# EU_Power_Management.net
KiCad netlist of a schematic drawn in Altium Designer
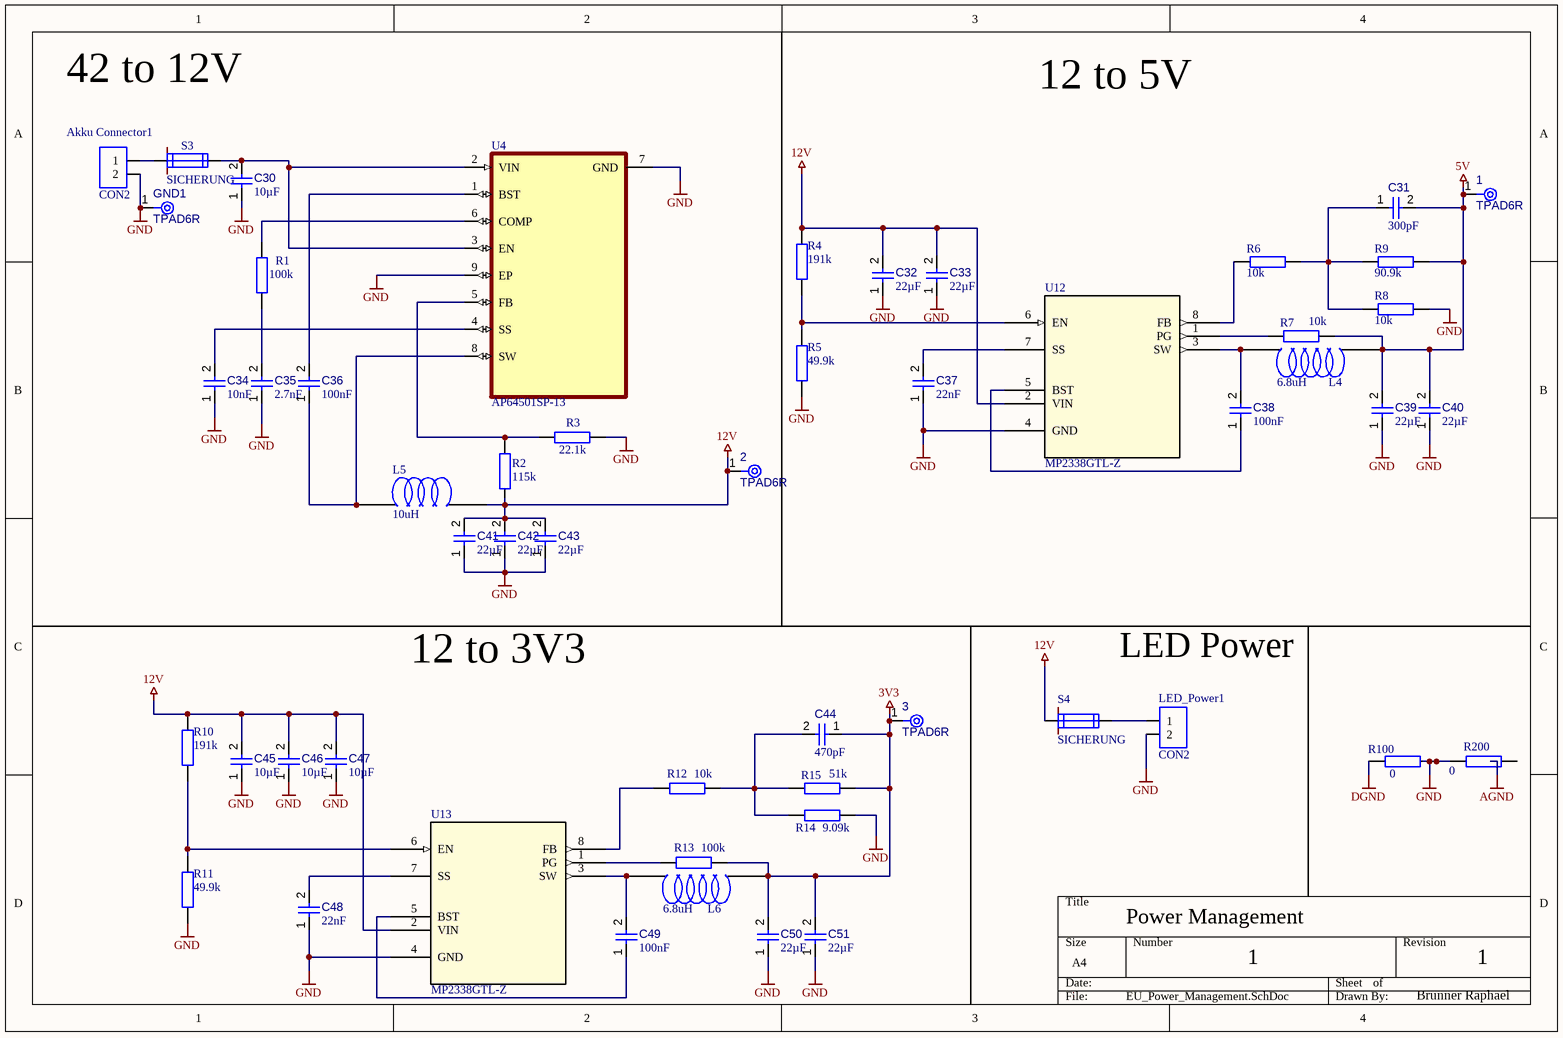
[diagram p0: EU_Power_Management.SchDoc]

(export (version "E")
  (design (tool "Eeschema 10.0.6"))
  (components
    (comp (ref "1")
      (value "TPAD6R")
      (footprint "TP06R")
      (description "0.6mm round")
      (libsource (lib " L-PRAN") (part "CMP-001-0001-4"))
    )
    (comp (ref "2")
      (value "TPAD6R")
      (footprint "TP06R")
      (description "0.6mm round")
      (libsource (lib " L-PRAN") (part "CMP-001-0001-4"))
    )
    (comp (ref "3")
      (value "TPAD6R")
      (footprint "TP06R")
      (description "0.6mm round")
      (libsource (lib " L-PRAN") (part "CMP-001-0001-4"))
    )
    (comp (ref "Akku Connector1")
      (value "CON2")
      (footprint "SIP-2")
      (description "Stecker")
      (libsource (lib "HTL-sym-2021_04") (part "CON2"))
    )
    (comp (ref "C30")
      (value "10µF")
      (footprint "CAPC0603(1608)100_L")
      (description "Chip Capacitor, 10µF +/-20%, 10V, 0603, Thickness 1 mm")
      (fields (field (name "TOLERANCE") "10%") (field (name "Comment") "Capacitor 10µF +/-20% 10V 0603"))
      (libsource (lib " L-PRAN") (part "CAP-NP-2"))
    )
    (comp (ref "C31")
      (value "300pF")
      (footprint "CAPC1608X90X40NL10T20")
      (description "Chip Capacitor, 100 nF, +/- 10%, 50 V, 0603 (1608 Metric)")
      (fields (field (name "TOLERANCE") "10%") (field (name "Comment") "Capacitor 100 nF +/-10% 50 V 0603"))
      (libsource (lib " L-PRAN") (part "CAP-NP-2"))
    )
    (comp (ref "C32")
      (value "22µF")
      (footprint "CAPC0805(2012)145_L")
      (description "Chip Capacitor, 22µF +/-40%, 16V, 0805, Thickness 1.45 mm")
      (fields (field (name "TOLERANCE") "5%") (field (name "Comment") "Capacitor 22µF +/-40% 16V 0805"))
      (libsource (lib " L-PRAN") (part "CAP-NP-2"))
    )
    (comp (ref "C33")
      (value "22µF")
      (footprint "CAPC0805(2012)145_L")
      (description "Chip Capacitor, 22µF +/-40%, 16V, 0805, Thickness 1.45 mm")
      (fields (field (name "TOLERANCE") "5%") (field (name "Comment") "Capacitor 22µF +/-40% 16V 0805"))
      (libsource (lib " L-PRAN") (part "CAP-NP-2"))
    )
    (comp (ref "C34")
      (value "10nF")
      (footprint "CAPC1608X94X35NL15T15")
      (description "Chip Capacitor, 1 uF, +/- 10%, 16 V, 0603 (1608 Metric)")
      (fields (field (name "TOLERANCE") "10%"))
      (libsource (lib " L-PRAN") (part "CAP-NP-2"))
    )
    (comp (ref "C35")
      (value "2.7nF")
      (footprint "CAPC1608X94X35NL15T15")
      (description "Chip Capacitor, 1 uF, +/- 10%, 16 V, 0603 (1608 Metric)")
      (fields (field (name "TOLERANCE") "10%"))
      (libsource (lib " L-PRAN") (part "CAP-NP-2"))
    )
    (comp (ref "C36")
      (value "100nF")
      (footprint "CAPC1608X94X35NL15T15")
      (description "Chip Capacitor, 1 uF, +/- 10%, 16 V, 0603 (1608 Metric)")
      (fields (field (name "TOLERANCE") "10%") (field (name "Comment") "0.1uF"))
      (libsource (lib " L-PRAN") (part "CAP-NP-2"))
    )
    (comp (ref "C37")
      (value "22nF")
      (footprint "CAPC0402(1005)60_L")
      (description "Chip Capacitor, 22nF +/-20%, 10V, 0402, Thickness 0.6 mm")
      (fields (field (name "TOLERANCE") "10%") (field (name "Comment") "Capacitor 22nF +/-20% 10V 0402"))
      (libsource (lib " L-PRAN") (part "CAP-NP-2"))
    )
    (comp (ref "C38")
      (value "100nF")
      (footprint "CAPC1608X90X40NL10T20")
      (description "Chip Capacitor, 100 nF, +/- 10%, 50 V, 0603 (1608 Metric)")
      (fields (field (name "TOLERANCE") "10%") (field (name "Comment") "Capacitor 100 nF +/-10% 50 V 0603"))
      (libsource (lib " L-PRAN") (part "CAP-NP-2"))
    )
    (comp (ref "C39")
      (value "22µF")
      (footprint "CAPC0805(2012)145_L")
      (description "Chip Capacitor, 22µF +/-40%, 16V, 0805, Thickness 1.45 mm")
      (fields (field (name "TOLERANCE") "5%") (field (name "Comment") "Capacitor 22µF +/-40% 16V 0805"))
      (libsource (lib " L-PRAN") (part "CAP-NP-2"))
    )
    (comp (ref "C40")
      (value "22µF")
      (footprint "CAPC0805(2012)145_L")
      (description "Chip Capacitor, 22µF +/-40%, 16V, 0805, Thickness 1.45 mm")
      (fields (field (name "TOLERANCE") "5%") (field (name "Comment") "Capacitor 22µF +/-40% 16V 0805"))
      (libsource (lib " L-PRAN") (part "CAP-NP-2"))
    )
    (comp (ref "C41")
      (value "22µF")
      (footprint "CAPC0805(2012)145_L")
      (description "Chip Capacitor, 22µF +/-40%, 16V, 0805, Thickness 1.45 mm")
      (fields (field (name "TOLERANCE") "5%") (field (name "Comment") "Capacitor 22µF +/-40% 16V 0805"))
      (libsource (lib " L-PRAN") (part "CAP-NP-2"))
    )
    (comp (ref "C42")
      (value "22µF")
      (footprint "CAPC0805(2012)145_L")
      (description "Chip Capacitor, 22µF +/-40%, 16V, 0805, Thickness 1.45 mm")
      (fields (field (name "TOLERANCE") "5%") (field (name "Comment") "Capacitor 22µF +/-40% 16V 0805"))
      (libsource (lib " L-PRAN") (part "CAP-NP-2"))
    )
    (comp (ref "C43")
      (value "22µF")
      (footprint "CAPC0805(2012)145_L")
      (description "Chip Capacitor, 22µF +/-40%, 16V, 0805, Thickness 1.45 mm")
      (fields (field (name "TOLERANCE") "5%") (field (name "Comment") "Capacitor 22µF +/-40% 16V 0805"))
      (libsource (lib " L-PRAN") (part "CAP-NP-2"))
    )
    (comp (ref "C44")
      (value "470pF")
      (footprint "CAPC1608X90X40NL10T20")
      (description "Chip Capacitor, 100 nF, +/- 10%, 50 V, 0603 (1608 Metric)")
      (fields (field (name "TOLERANCE") "10%") (field (name "Comment") "Capacitor 100 nF +/-10% 50 V 0603"))
      (libsource (lib " L-PRAN") (part "CAP-NP-2"))
    )
    (comp (ref "C45")
      (value "10µF")
      (footprint "CAPC0603(1608)100_L")
      (description "Chip Capacitor, 10µF +/-20%, 10V, 0603, Thickness 1 mm")
      (fields (field (name "TOLERANCE") "10%") (field (name "Comment") "Capacitor 10µF +/-20% 10V 0603"))
      (libsource (lib " L-PRAN") (part "CAP-NP-2"))
    )
    (comp (ref "C46")
      (value "10µF")
      (footprint "CAPC0603(1608)100_L")
      (description "Chip Capacitor, 10µF +/-20%, 10V, 0603, Thickness 1 mm")
      (fields (field (name "TOLERANCE") "10%") (field (name "Comment") "Capacitor 10µF +/-20% 10V 0603"))
      (libsource (lib " L-PRAN") (part "CAP-NP-2"))
    )
    (comp (ref "C47")
      (value "10µF")
      (footprint "CAPC0603(1608)100_L")
      (description "Chip Capacitor, 10µF +/-20%, 10V, 0603, Thickness 1 mm")
      (fields (field (name "TOLERANCE") "10%") (field (name "Comment") "Capacitor 10µF +/-20% 10V 0603"))
      (libsource (lib " L-PRAN") (part "CAP-NP-2"))
    )
    (comp (ref "C48")
      (value "22nF")
      (footprint "CAPC1608X90X40NL10T20")
      (description "Chip Capacitor, 100 nF, +/- 10%, 50 V, 0603 (1608 Metric)")
      (fields (field (name "TOLERANCE") "10%") (field (name "Comment") "Capacitor 100 nF +/-10% 50 V 0603"))
      (libsource (lib " L-PRAN") (part "CAP-NP-2"))
    )
    (comp (ref "C49")
      (value "100nF")
      (footprint "CAPC1608X90X40NL10T20")
      (description "Chip Capacitor, 100 nF, +/- 10%, 50 V, 0603 (1608 Metric)")
      (fields (field (name "TOLERANCE") "10%") (field (name "Comment") "Capacitor 100 nF +/-10% 50 V 0603"))
      (libsource (lib " L-PRAN") (part "CAP-NP-2"))
    )
    (comp (ref "C50")
      (value "22µF")
      (footprint "CAPC0805(2012)145_L")
      (description "Chip Capacitor, 22µF +/-40%, 16V, 0805, Thickness 1.45 mm")
      (fields (field (name "TOLERANCE") "5%") (field (name "Comment") "Capacitor 22µF +/-40% 16V 0805"))
      (libsource (lib " L-PRAN") (part "CAP-NP-2"))
    )
    (comp (ref "C51")
      (value "22µF")
      (footprint "CAPC0805(2012)145_L")
      (description "Chip Capacitor, 22µF +/-40%, 16V, 0805, Thickness 1.45 mm")
      (fields (field (name "TOLERANCE") "5%") (field (name "Comment") "Capacitor 22µF +/-40% 16V 0805"))
      (libsource (lib " L-PRAN") (part "CAP-NP-2"))
    )
    (comp (ref "GND1")
      (value "TPAD6R")
      (footprint "TP06R")
      (description "0.6mm round")
      (libsource (lib " L-PRAN") (part "CMP-001-0001-4"))
    )
    (comp (ref "L4")
      (value "6.8uH")
      (footprint "MPL-AL6060")
      (libsource (lib "Coil 6.8uH") (part "Component_1"))
    )
    (comp (ref "L5")
      (value "10uH")
      (footprint "MPL-AY1050")
      (libsource (lib "Coil 10uH") (part "Component_1"))
    )
    (comp (ref "L6")
      (value "6.8uH")
      (footprint "MPL-AL6060")
      (libsource (lib "Coil 6.8uH") (part "Component_1"))
    )
    (comp (ref "LED_Power1")
      (value "CON2")
      (footprint "SIP-2")
      (description "Stecker")
      (libsource (lib "HTL-sym-2021_04") (part "CON2"))
    )
    (comp (ref "R1")
      (value "100k")
      (footprint "Axial-0.4")
      (description "Widerstand")
      (fields (field (name "Comment") "RES"))
      (libsource (lib "HTL-sym-2021_04") (part "RES"))
    )
    (comp (ref "R2")
      (value "115k")
      (footprint "Axial-0.4")
      (description "Widerstand")
      (fields (field (name "Comment") "RES"))
      (libsource (lib "HTL-sym-2021_04") (part "RES"))
    )
    (comp (ref "R3")
      (value "22.1k")
      (footprint "Axial-0.4")
      (description "Widerstand")
      (fields (field (name "Comment") "RES"))
      (libsource (lib "HTL-sym-2021_04") (part "RES"))
    )
    (comp (ref "R4")
      (value "191k")
      (footprint "Axial-0.4")
      (description "Widerstand")
      (fields (field (name "Comment") "RES"))
      (libsource (lib "HTL-sym-2021_04") (part "RES"))
    )
    (comp (ref "R5")
      (value "49.9k")
      (footprint "Axial-0.4")
      (description "Widerstand")
      (fields (field (name "Comment") "RES"))
      (libsource (lib "HTL-sym-2021_04") (part "RES"))
    )
    (comp (ref "R6")
      (value "10k")
      (footprint "Axial-0.4")
      (description "Widerstand")
      (fields (field (name "Comment") "RES"))
      (libsource (lib "HTL-sym-2021_04") (part "RES"))
    )
    (comp (ref "R7")
      (value "10k")
      (footprint "Axial-0.4")
      (description "Widerstand")
      (fields (field (name "Comment") "RES"))
      (libsource (lib "HTL-sym-2021_04") (part "RES"))
    )
    (comp (ref "R8")
      (value "10k")
      (footprint "Axial-0.4")
      (description "Widerstand")
      (fields (field (name "Comment") "RES"))
      (libsource (lib "HTL-sym-2021_04") (part "RES"))
    )
    (comp (ref "R9")
      (value "90.9k")
      (footprint "Axial-0.4")
      (description "Widerstand")
      (fields (field (name "Comment") "RES"))
      (libsource (lib "HTL-sym-2021_04") (part "RES"))
    )
    (comp (ref "R10")
      (value "191k")
      (footprint "Axial-0.4")
      (description "Widerstand")
      (fields (field (name "Comment") "RES"))
      (libsource (lib "HTL-sym-2021_04") (part "RES"))
    )
    (comp (ref "R11")
      (value "49.9k")
      (footprint "Axial-0.4")
      (description "Widerstand")
      (fields (field (name "Comment") "RES"))
      (libsource (lib "HTL-sym-2021_04") (part "RES"))
    )
    (comp (ref "R12")
      (value "10k")
      (footprint "Axial-0.4")
      (description "Widerstand")
      (fields (field (name "Comment") "RES"))
      (libsource (lib "HTL-sym-2021_04") (part "RES"))
    )
    (comp (ref "R13")
      (value "100k")
      (footprint "Axial-0.4")
      (description "Widerstand")
      (fields (field (name "Comment") "RES"))
      (libsource (lib "HTL-sym-2021_04") (part "RES"))
    )
    (comp (ref "R14")
      (value "9.09k")
      (footprint "Axial-0.4")
      (description "Widerstand")
      (fields (field (name "Comment") "RES"))
      (libsource (lib "HTL-sym-2021_04") (part "RES"))
    )
    (comp (ref "R15")
      (value "51k")
      (footprint "Axial-0.4")
      (description "Widerstand")
      (fields (field (name "Comment") "RES"))
      (libsource (lib "HTL-sym-2021_04") (part "RES"))
    )
    (comp (ref "R100")
      (value "0")
      (footprint "Axial-0.4")
      (description "Widerstand")
      (fields (field (name "Comment") "RES"))
      (libsource (lib "HTL-sym-2021_04") (part "RES"))
    )
    (comp (ref "R200")
      (value "0")
      (footprint "Axial-0.4")
      (description "Widerstand")
      (fields (field (name "Comment") "RES"))
      (libsource (lib "HTL-sym-2021_04") (part "RES"))
    )
    (comp (ref "S3")
      (value "SICHERUNG")
      (footprint "SICHERUNG")
      (description "Sicherung")
      (libsource (lib "HTL-sym-2021_04") (part "SICHERUNG"))
    )
    (comp (ref "S4")
      (value "SICHERUNG")
      (footprint "SICHERUNG")
      (description "Sicherung")
      (libsource (lib "HTL-sym-2021_04") (part "SICHERUNG"))
    )
    (comp (ref "U4")
      (value "AP64501SP-13")
      (footprint "AP64501SP-13:SOIC127P600X170-9N")
      (fields (field (name "MF") "{'manufacturer': u'Diodes Incorporated'}"))
      (libsource (lib "*") (part "AP64501SP-13"))
    )
    (comp (ref "U12")
      (value "MP2338GTL-Z")
      (footprint "SOT583_MP2338_MNP")
      (description "High-Efficiency 28V 3A 450kHz Synchronous Step-Down Converter In SOT583 Package")
      (fields (field (name "COPYRIGHT") "Copyright (C) 2025 Ultra Librarian. All rights reserved."))
      (libsource (lib "MP2338GTL-Z") (part "MP2338GTL-Z"))
    )
    (comp (ref "U13")
      (value "MP2338GTL-Z")
      (footprint "SOT583_MP2338_MNP")
      (description "High-Efficiency 28V 3A 450kHz Synchronous Step-Down Converter In SOT583 Package")
      (fields (field (name "COPYRIGHT") "Copyright (C) 2025 Ultra Librarian. All rights reserved."))
      (libsource (lib "MP2338GTL-Z") (part "MP2338GTL-Z"))
    )
  )
  (nets
    (net (code "1") (name "3V3") (class "Default")
      (node (ref "3") (pin "1") (pinfunction "TP_1") (pintype "passive"))
      (node (ref "C44") (pin "1") (pinfunction "1_1") (pintype "passive"))
      (node (ref "C50") (pin "2") (pinfunction "2_2") (pintype "passive"))
      (node (ref "C51") (pin "2") (pinfunction "2_2") (pintype "passive"))
      (node (ref "L6") (pin "2") (pinfunction "2_2") (pintype "passive"))
      (node (ref "R13") (pin "2") (pintype "passive"))
      (node (ref "R15") (pin "2") (pintype "passive"))
    )
    (net (code "2") (name "5V") (class "Default")
      (node (ref "1") (pin "1") (pinfunction "TP_1") (pintype "passive"))
      (node (ref "C31") (pin "2") (pinfunction "2_2") (pintype "passive"))
      (node (ref "C39") (pin "2") (pinfunction "2_2") (pintype "passive"))
      (node (ref "C40") (pin "2") (pinfunction "2_2") (pintype "passive"))
      (node (ref "L4") (pin "2") (pinfunction "2_2") (pintype "passive"))
      (node (ref "R7") (pin "1") (pintype "passive"))
      (node (ref "R9") (pin "1") (pintype "passive"))
    )
    (net (code "3") (name "12V") (class "Default")
      (node (ref "2") (pin "1") (pinfunction "TP_1") (pintype "passive"))
      (node (ref "C32") (pin "2") (pinfunction "2_2") (pintype "passive"))
      (node (ref "C33") (pin "2") (pinfunction "2_2") (pintype "passive"))
      (node (ref "C41") (pin "2") (pinfunction "2_2") (pintype "passive"))
      (node (ref "C42") (pin "2") (pinfunction "2_2") (pintype "passive"))
      (node (ref "C43") (pin "2") (pinfunction "2_2") (pintype "passive"))
      (node (ref "C45") (pin "2") (pinfunction "2_2") (pintype "passive"))
      (node (ref "C46") (pin "2") (pinfunction "2_2") (pintype "passive"))
      (node (ref "C47") (pin "2") (pinfunction "2_2") (pintype "passive"))
      (node (ref "L5") (pin "2") (pinfunction "2_2") (pintype "passive"))
      (node (ref "R10") (pin "1") (pintype "passive"))
      (node (ref "R2") (pin "2") (pintype "passive"))
      (node (ref "R4") (pin "2") (pintype "passive"))
      (node (ref "S4") (pin "1") (pintype "passive"))
      (node (ref "U12") (pin "2") (pinfunction "VIN_2") (pintype "power_in"))
      (node (ref "U13") (pin "2") (pinfunction "VIN_2") (pintype "power_in"))
    )
    (net (code "5") (name "DGND") (class "Default") (node (ref "R100") (pin "1") (pintype "passive")))
    (net (code "6") (name "GND") (class "Default")
      (node (ref "Akku Connector1") (pin "2") (pinfunction "2_2") (pintype "passive"))
      (node (ref "C30") (pin "1") (pinfunction "1_1") (pintype "passive"))
      (node (ref "C32") (pin "1") (pinfunction "1_1") (pintype "passive"))
      (node (ref "C33") (pin "1") (pinfunction "1_1") (pintype "passive"))
      (node (ref "C34") (pin "1") (pinfunction "1_1") (pintype "passive"))
      (node (ref "C35") (pin "1") (pinfunction "1_1") (pintype "passive"))
      (node (ref "C37") (pin "1") (pinfunction "1_1") (pintype "passive"))
      (node (ref "C39") (pin "1") (pinfunction "1_1") (pintype "passive"))
      (node (ref "C40") (pin "1") (pinfunction "1_1") (pintype "passive"))
      (node (ref "C41") (pin "1") (pinfunction "1_1") (pintype "passive"))
      (node (ref "C42") (pin "1") (pinfunction "1_1") (pintype "passive"))
      (node (ref "C43") (pin "1") (pinfunction "1_1") (pintype "passive"))
      (node (ref "C45") (pin "1") (pinfunction "1_1") (pintype "passive"))
      (node (ref "C46") (pin "1") (pinfunction "1_1") (pintype "passive"))
      (node (ref "C47") (pin "1") (pinfunction "1_1") (pintype "passive"))
      (node (ref "C48") (pin "1") (pinfunction "1_1") (pintype "passive"))
      (node (ref "C50") (pin "1") (pinfunction "1_1") (pintype "passive"))
      (node (ref "C51") (pin "1") (pinfunction "1_1") (pintype "passive"))
      (node (ref "GND1") (pin "1") (pinfunction "TP_1") (pintype "passive"))
      (node (ref "LED_Power1") (pin "2") (pinfunction "2_2") (pintype "passive"))
      (node (ref "R100") (pin "2") (pintype "passive"))
      (node (ref "R11") (pin "2") (pintype "passive"))
      (node (ref "R14") (pin "2") (pintype "passive"))
      (node (ref "R200") (pin "1") (pintype "passive"))
      (node (ref "R3") (pin "2") (pintype "passive"))
      (node (ref "R5") (pin "1") (pintype "passive"))
      (node (ref "R8") (pin "1") (pintype "passive"))
      (node (ref "U12") (pin "4") (pinfunction "GND_4") (pintype "power_in"))
      (node (ref "U13") (pin "4") (pinfunction "GND_4") (pintype "power_in"))
      (node (ref "U4") (pin "7") (pinfunction "GND_7") (pintype "power_in"))
      (node (ref "U4") (pin "9") (pinfunction "EP_9") (pintype "bidirectional"))
    )
    (net (code "7") (name "Net-(Akku Connector1-Pad1)") (class "Default")
      (node (ref "Akku Connector1") (pin "1") (pinfunction "1_1") (pintype "passive"))
      (node (ref "S3") (pin "1") (pintype "passive"))
    )
    (net (code "8") (name "Net-(C31-Pad1)") (class "Default")
      (node (ref "C31") (pin "1") (pinfunction "1_1") (pintype "passive"))
      (node (ref "R6") (pin "1") (pintype "passive"))
      (node (ref "R8") (pin "2") (pintype "passive"))
      (node (ref "R9") (pin "2") (pintype "passive"))
    )
    (net (code "9") (name "Net-(C35-Pad2)") (class "Default")
      (node (ref "C35") (pin "2") (pinfunction "2_2") (pintype "passive"))
      (node (ref "R1") (pin "2") (pintype "passive"))
    )
    (net (code "10") (name "Net-(C44-Pad2)") (class "Default")
      (node (ref "C44") (pin "2") (pinfunction "2_2") (pintype "passive"))
      (node (ref "R12") (pin "2") (pintype "passive"))
      (node (ref "R14") (pin "1") (pintype "passive"))
      (node (ref "R15") (pin "1") (pintype "passive"))
    )
    (net (code "11") (name "Net-(LED_Power1-Pad1)") (class "Default")
      (node (ref "LED_Power1") (pin "1") (pinfunction "1_1") (pintype "passive"))
      (node (ref "S4") (pin "2") (pinfunction "2_2") (pintype "passive"))
    )
    (net (code "12") (name "Net-(U4-BST)") (class "Default")
      (node (ref "C36") (pin "2") (pinfunction "2_2") (pintype "passive"))
      (node (ref "U4") (pin "1") (pinfunction "BST_1") (pintype "bidirectional"))
    )
    (net (code "13") (name "Net-(U4-COMP)") (class "Default")
      (node (ref "R1") (pin "1") (pintype "passive"))
      (node (ref "U4") (pin "6") (pinfunction "COMP_6") (pintype "bidirectional"))
    )
    (net (code "14") (name "Net-(U4-EN)") (class "Default")
      (node (ref "C30") (pin "2") (pinfunction "2_2") (pintype "passive"))
      (node (ref "S3") (pin "2") (pinfunction "2_2") (pintype "passive"))
      (node (ref "U4") (pin "2") (pinfunction "VIN_2") (pintype "input"))
      (node (ref "U4") (pin "3") (pinfunction "EN_3") (pintype "bidirectional"))
    )
    (net (code "15") (name "Net-(U4-FB)") (class "Default")
      (node (ref "R2") (pin "1") (pintype "passive"))
      (node (ref "R3") (pin "1") (pintype "passive"))
      (node (ref "U4") (pin "5") (pinfunction "FB_5") (pintype "bidirectional"))
    )
    (net (code "16") (name "Net-(U4-SS)") (class "Default")
      (node (ref "C34") (pin "2") (pinfunction "2_2") (pintype "passive"))
      (node (ref "U4") (pin "4") (pinfunction "SS_4") (pintype "bidirectional"))
    )
    (net (code "17") (name "Net-(U4-SW)") (class "Default")
      (node (ref "C36") (pin "1") (pinfunction "1_1") (pintype "passive"))
      (node (ref "L5") (pin "1") (pinfunction "1_1") (pintype "passive"))
      (node (ref "U4") (pin "8") (pinfunction "SW_8") (pintype "bidirectional"))
    )
    (net (code "18") (name "Net-(U12-BST)") (class "Default")
      (node (ref "C38") (pin "1") (pinfunction "1_1") (pintype "passive"))
      (node (ref "U12") (pin "5") (pinfunction "BST_5") (pintype "power_in"))
    )
    (net (code "19") (name "Net-(U12-EN)") (class "Default")
      (node (ref "R4") (pin "1") (pintype "passive"))
      (node (ref "R5") (pin "2") (pintype "passive"))
      (node (ref "U12") (pin "6") (pinfunction "EN_6") (pintype "input"))
    )
    (net (code "20") (name "Net-(U12-FB)") (class "Default")
      (node (ref "R6") (pin "2") (pintype "passive"))
      (node (ref "U12") (pin "8") (pinfunction "FB_8") (pintype "output"))
    )
    (net (code "21") (name "Net-(U12-PG)") (class "Default")
      (node (ref "R7") (pin "2") (pintype "passive"))
      (node (ref "U12") (pin "1") (pinfunction "PG_1") (pintype "output"))
    )
    (net (code "22") (name "Net-(U12-SS)") (class "Default")
      (node (ref "C37") (pin "2") (pinfunction "2_2") (pintype "passive"))
      (node (ref "U12") (pin "7") (pinfunction "SS_7") (pintype "passive"))
    )
    (net (code "23") (name "Net-(U12-SW)") (class "Default")
      (node (ref "C38") (pin "2") (pinfunction "2_2") (pintype "passive"))
      (node (ref "L4") (pin "1") (pinfunction "1_1") (pintype "passive"))
      (node (ref "U12") (pin "3") (pinfunction "SW_3") (pintype "output"))
    )
    (net (code "24") (name "Net-(U13-BST)") (class "Default")
      (node (ref "C49") (pin "1") (pinfunction "1_1") (pintype "passive"))
      (node (ref "U13") (pin "5") (pinfunction "BST_5") (pintype "power_in"))
    )
    (net (code "25") (name "Net-(U13-EN)") (class "Default")
      (node (ref "R10") (pin "2") (pintype "passive"))
      (node (ref "R11") (pin "1") (pintype "passive"))
      (node (ref "U13") (pin "6") (pinfunction "EN_6") (pintype "input"))
    )
    (net (code "26") (name "Net-(U13-FB)") (class "Default")
      (node (ref "R12") (pin "1") (pintype "passive"))
      (node (ref "U13") (pin "8") (pinfunction "FB_8") (pintype "output"))
    )
    (net (code "27") (name "Net-(U13-PG)") (class "Default")
      (node (ref "R13") (pin "1") (pintype "passive"))
      (node (ref "U13") (pin "1") (pinfunction "PG_1") (pintype "output"))
    )
    (net (code "28") (name "Net-(U13-SS)") (class "Default")
      (node (ref "C48") (pin "2") (pinfunction "2_2") (pintype "passive"))
      (node (ref "U13") (pin "7") (pinfunction "SS_7") (pintype "passive"))
    )
    (net (code "29") (name "Net-(U13-SW)") (class "Default")
      (node (ref "C49") (pin "2") (pinfunction "2_2") (pintype "passive"))
      (node (ref "L6") (pin "1") (pinfunction "1_1") (pintype "passive"))
      (node (ref "U13") (pin "3") (pinfunction "SW_3") (pintype "output"))
    )
    (net (code "30") (name "unconnected-(R200-Pad2)") (class "Default")
      (node (ref "R200") (pin "2") (pintype "passive"))
    )
  )
)
